# WaterDepthAnalysisBoardv2.net
KiCad netlist of a schematic drawn in Altium Designer
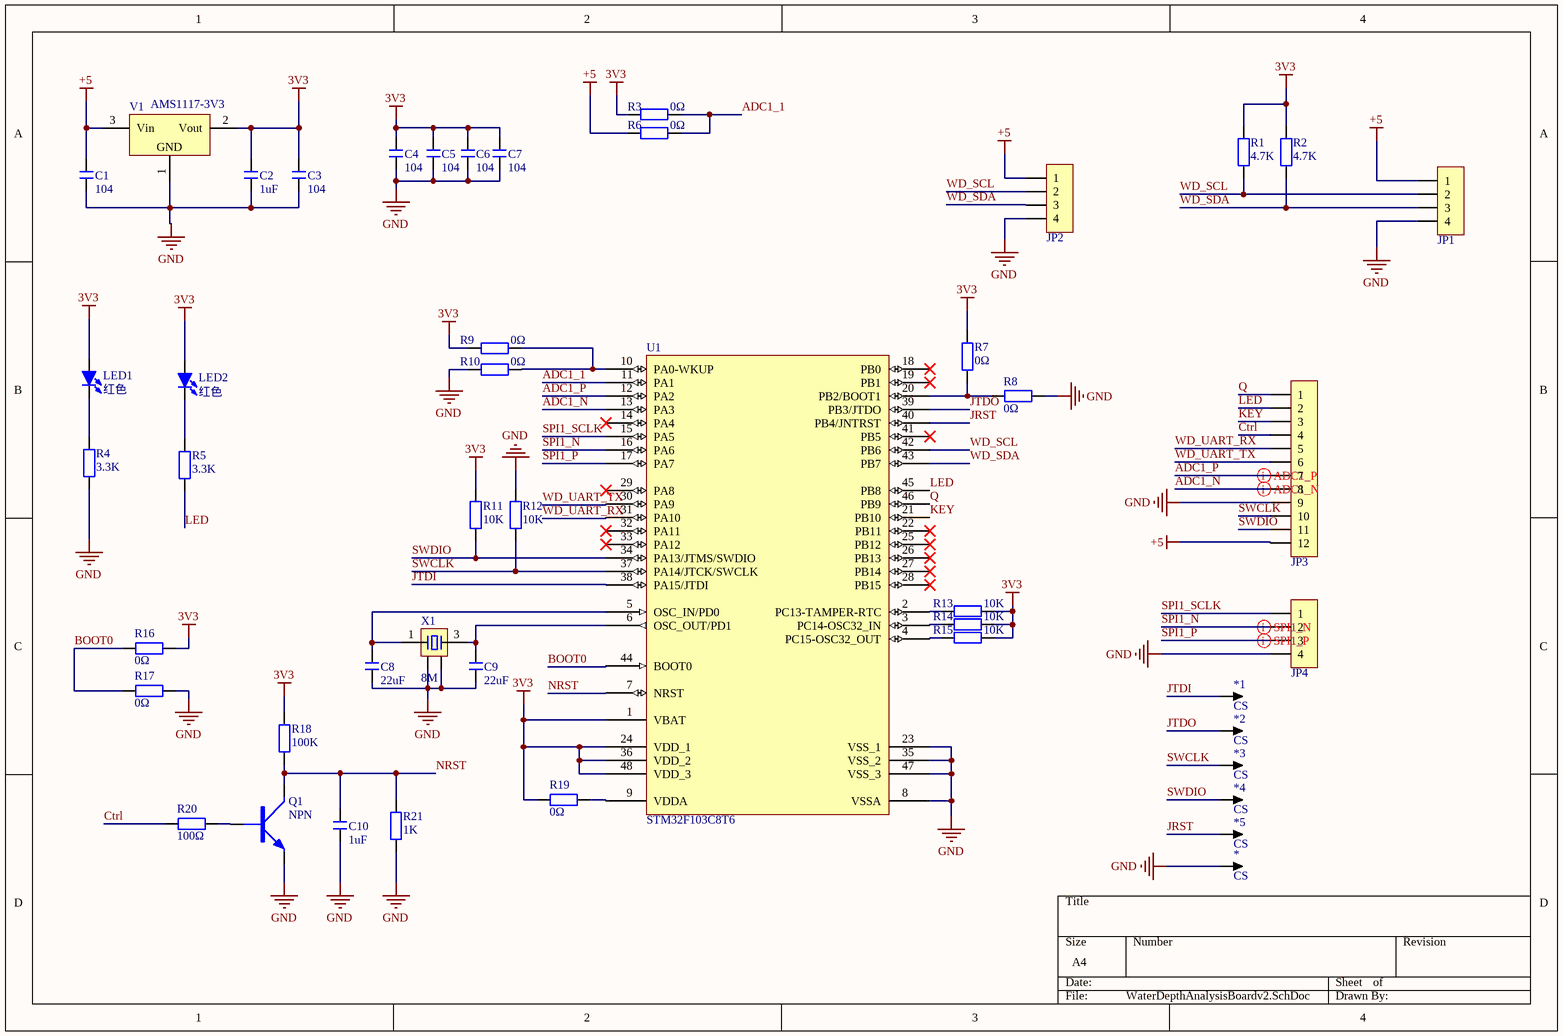
[diagram p0: WaterDepthAnalysisBoardv2.SchDoc]

(export (version "E")
  (design (tool "Eeschema 10.0.6"))
  (components
    (comp (ref "*")
      (value "CS")
      (footprint "R100")
      (description "探针焊盘")
      (fields (field (name "版权归属") "源创客"))
      (libsource (lib "15.1 - 未分类器件") (part "CS"))
    )
    (comp (ref "*1")
      (value "CS")
      (footprint "R100")
      (description "探针焊盘")
      (fields (field (name "版权归属") "源创客"))
      (libsource (lib "15.1 - 未分类器件") (part "CS"))
    )
    (comp (ref "*2")
      (value "CS")
      (footprint "R100")
      (description "探针焊盘")
      (fields (field (name "版权归属") "源创客"))
      (libsource (lib "15.1 - 未分类器件") (part "CS"))
    )
    (comp (ref "*3")
      (value "CS")
      (footprint "R100")
      (description "探针焊盘")
      (fields (field (name "版权归属") "源创客"))
      (libsource (lib "15.1 - 未分类器件") (part "CS"))
    )
    (comp (ref "*4")
      (value "CS")
      (footprint "R100")
      (description "探针焊盘")
      (fields (field (name "版权归属") "源创客"))
      (libsource (lib "15.1 - 未分类器件") (part "CS"))
    )
    (comp (ref "*5")
      (value "CS")
      (footprint "R100")
      (description "探针焊盘")
      (fields (field (name "版权归属") "源创客"))
      (libsource (lib "15.1 - 未分类器件") (part "CS"))
    )
    (comp (ref "C1")
      (value "104")
      (footprint "C 0603_L")
      (description "无极性贴片电容")
      (fields (field (name "版权归属") "源创客"))
      (libsource (lib "3.1   - 电阻-电容-电感") (part "C"))
    )
    (comp (ref "C2")
      (value "1uF")
      (footprint "C 0603_L")
      (description "无极性贴片电容")
      (fields (field (name "版权归属") "源创客"))
      (libsource (lib "3.1   - 电阻-电容-电感") (part "C"))
    )
    (comp (ref "C3")
      (value "104")
      (footprint "C 0603_L")
      (description "无极性贴片电容")
      (fields (field (name "版权归属") "源创客"))
      (libsource (lib "3.1   - 电阻-电容-电感") (part "C"))
    )
    (comp (ref "C4")
      (value "104")
      (footprint "C 0603_L")
      (description "无极性贴片电容")
      (fields (field (name "版权归属") "源创客"))
      (libsource (lib "3.1   - 电阻-电容-电感") (part "C"))
    )
    (comp (ref "C5")
      (value "104")
      (footprint "C 0603_L")
      (description "无极性贴片电容")
      (fields (field (name "版权归属") "源创客"))
      (libsource (lib "3.1   - 电阻-电容-电感") (part "C"))
    )
    (comp (ref "C6")
      (value "104")
      (footprint "C 0603_L")
      (description "无极性贴片电容")
      (fields (field (name "版权归属") "源创客"))
      (libsource (lib "3.1   - 电阻-电容-电感") (part "C"))
    )
    (comp (ref "C7")
      (value "104")
      (footprint "C 0603_L")
      (description "无极性贴片电容")
      (fields (field (name "版权归属") "源创客"))
      (libsource (lib "3.1   - 电阻-电容-电感") (part "C"))
    )
    (comp (ref "C8")
      (value "22uF")
      (footprint "C 0603_L")
      (description "无极性贴片电容")
      (fields (field (name "版权归属") "源创客"))
      (libsource (lib "3.1   - 电阻-电容-电感") (part "C"))
    )
    (comp (ref "C9")
      (value "22uF")
      (footprint "C 0603_L")
      (description "无极性贴片电容")
      (fields (field (name "版权归属") "源创客"))
      (libsource (lib "3.1   - 电阻-电容-电感") (part "C"))
    )
    (comp (ref "C10")
      (value "1uF")
      (footprint "C 0603_L")
      (description "无极性贴片电容")
      (fields (field (name "版权归属") "源创客"))
      (libsource (lib "3.1   - 电阻-电容-电感") (part "C"))
    )
    (comp (ref "JP1")
      (value "HDR-1X4")
      (footprint "MX 1.25-LI-4P")
      (description "4P接插件")
      (fields (field (name "版权归属") "源创客"))
      (libsource (lib "4.2   - 接插件-脚距1.25") (part "Header 4"))
    )
    (comp (ref "JP2")
      (value "HDR-1X4")
      (footprint "MX 1.25-LS-4P")
      (description "4P接插件")
      (fields (field (name "版权归属") "源创客"))
      (libsource (lib "4.2   - 接插件-脚距1.25") (part "Header 4"))
    )
    (comp (ref "JP3")
      (value "HDR-1X12")
      (footprint "HDR2.54-LI-12P")
      (description "12P接插件")
      (fields (field (name "版权归属") "源创客"))
      (libsource (lib "4.5   - 接插件-脚距2.54") (part "Header 12"))
    )
    (comp (ref "JP4")
      (value "HDR-1X4")
      (footprint "HDR2.54-LI-4P")
      (description "4P接插件")
      (fields (field (name "版权归属") "源创客"))
      (libsource (lib "4.5   - 接插件-脚距2.54") (part "Header 4"))
    )
    (comp (ref "LED1")
      (value "红色")
      (footprint "LED 0603W")
      (description "贴片LED")
      (fields (field (name "版权归属") "源创客"))
      (libsource (lib "9.1   - LED") (part "LED-SMD"))
    )
    (comp (ref "LED2")
      (value "红色")
      (footprint "LED 0603W")
      (description "贴片LED")
      (fields (field (name "版权归属") "源创客"))
      (libsource (lib "9.1   - LED") (part "LED-SMD"))
    )
    (comp (ref "Q1")
      (value "NPN")
      (footprint "SOT-23")
      (description "NPN三极管")
      (libsource (lib "三极管") (part "NPN"))
    )
    (comp (ref "R1")
      (value "4.7K")
      (footprint "R 0603_L")
      (description "贴片电阻")
      (fields (field (name "版权归属") "源创客"))
      (libsource (lib "3.1   - 电阻-电容-电感") (part "R"))
    )
    (comp (ref "R2")
      (value "4.7K")
      (footprint "R 0603_L")
      (description "贴片电阻")
      (fields (field (name "版权归属") "源创客"))
      (libsource (lib "3.1   - 电阻-电容-电感") (part "R"))
    )
    (comp (ref "R3")
      (value "0Ω")
      (footprint "R 0603_L")
      (description "贴片电阻")
      (fields (field (name "版权归属") "源创客"))
      (libsource (lib "3.1   - 电阻-电容-电感") (part "R"))
    )
    (comp (ref "R4")
      (value "3.3K")
      (footprint "R 0603_L")
      (description "贴片电阻")
      (fields (field (name "版权归属") "源创客"))
      (libsource (lib "3.1   - 电阻-电容-电感") (part "R"))
    )
    (comp (ref "R5")
      (value "3.3K")
      (footprint "R 0603_L")
      (description "贴片电阻")
      (fields (field (name "版权归属") "源创客"))
      (libsource (lib "3.1   - 电阻-电容-电感") (part "R"))
    )
    (comp (ref "R6")
      (value "0Ω")
      (footprint "R 0603_L")
      (description "贴片电阻")
      (fields (field (name "版权归属") "源创客"))
      (libsource (lib "3.1   - 电阻-电容-电感") (part "R"))
    )
    (comp (ref "R7")
      (value "0Ω")
      (footprint "R 0603_L")
      (description "贴片电阻")
      (fields (field (name "版权归属") "源创客"))
      (libsource (lib "3.1   - 电阻-电容-电感") (part "R"))
    )
    (comp (ref "R8")
      (value "0Ω")
      (footprint "R 0603_L")
      (description "贴片电阻")
      (fields (field (name "版权归属") "源创客"))
      (libsource (lib "3.1   - 电阻-电容-电感") (part "R"))
    )
    (comp (ref "R9")
      (value "0Ω")
      (footprint "R 0603_L")
      (description "贴片电阻")
      (fields (field (name "版权归属") "源创客"))
      (libsource (lib "3.1   - 电阻-电容-电感") (part "R"))
    )
    (comp (ref "R10")
      (value "0Ω")
      (footprint "R 0603_L")
      (description "贴片电阻")
      (fields (field (name "版权归属") "源创客"))
      (libsource (lib "3.1   - 电阻-电容-电感") (part "R"))
    )
    (comp (ref "R11")
      (value "10K")
      (footprint "R 0603_L")
      (description "贴片电阻")
      (fields (field (name "版权归属") "源创客"))
      (libsource (lib "3.1   - 电阻-电容-电感") (part "R"))
    )
    (comp (ref "R12")
      (value "10K")
      (footprint "R 0603_L")
      (description "贴片电阻")
      (fields (field (name "版权归属") "源创客"))
      (libsource (lib "3.1   - 电阻-电容-电感") (part "R"))
    )
    (comp (ref "R13")
      (value "10K")
      (footprint "R 0603_L")
      (description "贴片电阻")
      (fields (field (name "版权归属") "源创客"))
      (libsource (lib "3.1   - 电阻-电容-电感") (part "R"))
    )
    (comp (ref "R14")
      (value "10K")
      (footprint "R 0603_L")
      (description "贴片电阻")
      (fields (field (name "版权归属") "源创客"))
      (libsource (lib "3.1   - 电阻-电容-电感") (part "R"))
    )
    (comp (ref "R15")
      (value "10K")
      (footprint "R 0603_L")
      (description "贴片电阻")
      (fields (field (name "版权归属") "源创客"))
      (libsource (lib "3.1   - 电阻-电容-电感") (part "R"))
    )
    (comp (ref "R16")
      (value "0Ω")
      (footprint "R 0603_L")
      (description "贴片电阻")
      (fields (field (name "版权归属") "源创客"))
      (libsource (lib "3.1   - 电阻-电容-电感") (part "R"))
    )
    (comp (ref "R17")
      (value "0Ω")
      (footprint "R 0603_L")
      (description "贴片电阻")
      (fields (field (name "版权归属") "源创客"))
      (libsource (lib "3.1   - 电阻-电容-电感") (part "R"))
    )
    (comp (ref "R18")
      (value "100K")
      (footprint "R 0603_L")
      (description "贴片电阻")
      (fields (field (name "版权归属") "源创客"))
      (libsource (lib "3.1   - 电阻-电容-电感") (part "R"))
    )
    (comp (ref "R19")
      (value "0Ω")
      (footprint "R 0603_L")
      (description "贴片电阻")
      (fields (field (name "版权归属") "源创客"))
      (libsource (lib "3.1   - 电阻-电容-电感") (part "R"))
    )
    (comp (ref "R20")
      (value "100Ω")
      (footprint "R 0603_L")
      (description "贴片电阻")
      (fields (field (name "版权归属") "源创客"))
      (libsource (lib "3.1   - 电阻-电容-电感") (part "R"))
    )
    (comp (ref "R21")
      (value "1K")
      (footprint "R 0603_L")
      (description "贴片电阻")
      (fields (field (name "版权归属") "源创客"))
      (libsource (lib "3.1   - 电阻-电容-电感") (part "R"))
    )
    (comp (ref "U1")
      (value "STM32F103C8T6")
      (footprint "LQFP48 7X7")
      (libsource (lib "STM32系列") (part "STM32F103C8T6"))
    )
    (comp (ref "V1")
      (value "AMS1117-3V3")
      (footprint "SOT89_N")
      (description "三端稳压芯片")
      (fields (field (name "版权归属") "源创客"))
      (libsource (lib "1.3   - 电源类芯片") (part "AMS1117"))
    )
    (comp (ref "X1")
      (value "8M")
      (footprint "OSC 5032-4P")
      (description "4脚无源晶振")
      (fields (field (name "版权归属") "源创客"))
      (libsource (lib "10.1 - 保险丝-晶振") (part "XTAL-4P"))
    )
  )
  (nets
    (net (code "1") (name "+5") (class "Default")
      (node (ref "C1") (pin "2") (pinfunction "2_2") (pintype "passive"))
      (node (ref "JP1") (pin "1") (pinfunction "1_1") (pintype "passive"))
      (node (ref "JP2") (pin "1") (pinfunction "1_1") (pintype "passive"))
      (node (ref "JP3") (pin "12") (pinfunction "12_12") (pintype "passive"))
      (node (ref "R6") (pin "2") (pinfunction "2_2") (pintype "passive"))
      (node (ref "V1") (pin "3") (pinfunction "Vin_3") (pintype "passive"))
    )
    (net (code "2") (name "/ADC1_1") (class "Default")
      (node (ref "R3") (pin "1") (pinfunction "1_1") (pintype "passive"))
      (node (ref "R6") (pin "1") (pinfunction "1_1") (pintype "passive"))
      (node (ref "U1") (pin "11") (pinfunction "PA1_11") (pintype "bidirectional"))
    )
    (net (code "3") (name "/ADC1_N") (class "Default")
      (node (ref "JP3") (pin "8") (pinfunction "8_8") (pintype "passive"))
      (node (ref "U1") (pin "13") (pinfunction "PA3_13") (pintype "bidirectional"))
    )
    (net (code "4") (name "/ADC1_P") (class "Default")
      (node (ref "JP3") (pin "7") (pinfunction "7_7") (pintype "passive"))
      (node (ref "U1") (pin "12") (pinfunction "PA2_12") (pintype "bidirectional"))
    )
    (net (code "5") (name "/BOOT0") (class "Default")
      (node (ref "R16") (pin "2") (pinfunction "2_2") (pintype "passive"))
      (node (ref "R17") (pin "2") (pinfunction "2_2") (pintype "passive"))
      (node (ref "U1") (pin "44") (pinfunction "BOOT0_44") (pintype "input"))
    )
    (net (code "6") (name "/Ctrl") (class "Default")
      (node (ref "JP3") (pin "4") (pinfunction "4_4") (pintype "passive"))
      (node (ref "R20") (pin "2") (pinfunction "2_2") (pintype "passive"))
    )
    (net (code "7") (name "/JRST") (class "Default")
      (node (ref "*5") (pin "1") (pinfunction "1_1") (pintype "passive"))
      (node (ref "U1") (pin "40") (pinfunction "PB4/JNTRST_40") (pintype "bidirectional"))
    )
    (net (code "8") (name "/JTDI") (class "Default")
      (node (ref "*1") (pin "1") (pinfunction "1_1") (pintype "passive"))
      (node (ref "U1") (pin "38") (pinfunction "PA15/JTDI_38") (pintype "bidirectional"))
    )
    (net (code "9") (name "/JTDO") (class "Default")
      (node (ref "*2") (pin "1") (pinfunction "1_1") (pintype "passive"))
      (node (ref "U1") (pin "39") (pinfunction "PB3/JTDO_39") (pintype "bidirectional"))
    )
    (net (code "10") (name "/KEY") (class "Default")
      (node (ref "JP3") (pin "3") (pinfunction "3_3") (pintype "passive"))
      (node (ref "U1") (pin "21") (pinfunction "PB10_21") (pintype "bidirectional"))
    )
    (net (code "11") (name "/LED") (class "Default")
      (node (ref "JP3") (pin "2") (pinfunction "2_2") (pintype "passive"))
      (node (ref "R5") (pin "1") (pinfunction "1_1") (pintype "passive"))
      (node (ref "U1") (pin "45") (pinfunction "PB8_45") (pintype "bidirectional"))
    )
    (net (code "12") (name "/NRST") (class "Default")
      (node (ref "C10") (pin "2") (pinfunction "2_2") (pintype "passive"))
      (node (ref "Q1") (pin "C") (pinfunction "C_C") (pintype "passive"))
      (node (ref "R18") (pin "2") (pinfunction "2_2") (pintype "passive"))
      (node (ref "R21") (pin "1") (pinfunction "1_1") (pintype "passive"))
      (node (ref "U1") (pin "7") (pinfunction "NRST_7") (pintype "bidirectional"))
    )
    (net (code "13") (name "/Q") (class "Default")
      (node (ref "JP3") (pin "1") (pinfunction "1_1") (pintype "passive"))
      (node (ref "U1") (pin "46") (pinfunction "PB9_46") (pintype "bidirectional"))
    )
    (net (code "14") (name "/SPI1_N") (class "Default")
      (node (ref "JP4") (pin "2") (pinfunction "2_2") (pintype "passive"))
      (node (ref "U1") (pin "16") (pinfunction "PA6_16") (pintype "bidirectional"))
    )
    (net (code "15") (name "/SPI1_P") (class "Default")
      (node (ref "JP4") (pin "3") (pinfunction "3_3") (pintype "passive"))
      (node (ref "U1") (pin "17") (pinfunction "PA7_17") (pintype "bidirectional"))
    )
    (net (code "16") (name "/SPI1_SCLK") (class "Default")
      (node (ref "JP4") (pin "1") (pinfunction "1_1") (pintype "passive"))
      (node (ref "U1") (pin "15") (pinfunction "PA5_15") (pintype "bidirectional"))
    )
    (net (code "17") (name "/SWCLK") (class "Default")
      (node (ref "*3") (pin "1") (pinfunction "1_1") (pintype "passive"))
      (node (ref "JP3") (pin "10") (pinfunction "10_10") (pintype "passive"))
      (node (ref "R12") (pin "2") (pinfunction "2_2") (pintype "passive"))
      (node (ref "U1") (pin "37") (pinfunction "PA14/JTCK/SWCLK_37") (pintype "bidirectional"))
    )
    (net (code "18") (name "/SWDIO") (class "Default")
      (node (ref "*4") (pin "1") (pinfunction "1_1") (pintype "passive"))
      (node (ref "JP3") (pin "11") (pinfunction "11_11") (pintype "passive"))
      (node (ref "R11") (pin "2") (pinfunction "2_2") (pintype "passive"))
      (node (ref "U1") (pin "34") (pinfunction "PA13/JTMS/SWDIO_34") (pintype "bidirectional"))
    )
    (net (code "19") (name "/WD_SCL") (class "Default")
      (node (ref "JP1") (pin "2") (pinfunction "2_2") (pintype "passive"))
      (node (ref "JP2") (pin "2") (pinfunction "2_2") (pintype "passive"))
      (node (ref "R1") (pin "1") (pinfunction "1_1") (pintype "passive"))
      (node (ref "U1") (pin "42") (pinfunction "PB6_42") (pintype "bidirectional"))
    )
    (net (code "20") (name "/WD_SDA") (class "Default")
      (node (ref "JP1") (pin "3") (pinfunction "3_3") (pintype "passive"))
      (node (ref "JP2") (pin "3") (pinfunction "3_3") (pintype "passive"))
      (node (ref "R2") (pin "1") (pinfunction "1_1") (pintype "passive"))
      (node (ref "U1") (pin "43") (pinfunction "PB7_43") (pintype "bidirectional"))
    )
    (net (code "21") (name "/WD_UART_RX") (class "Default")
      (node (ref "JP3") (pin "5") (pinfunction "5_5") (pintype "passive"))
      (node (ref "U1") (pin "31") (pinfunction "PA10_31") (pintype "bidirectional"))
    )
    (net (code "22") (name "/WD_UART_TX") (class "Default")
      (node (ref "JP3") (pin "6") (pinfunction "6_6") (pintype "passive"))
      (node (ref "U1") (pin "30") (pinfunction "PA9_30") (pintype "bidirectional"))
    )
    (net (code "23") (name "3V3") (class "Default")
      (node (ref "C2") (pin "2") (pinfunction "2_2") (pintype "passive"))
      (node (ref "C3") (pin "2") (pinfunction "2_2") (pintype "passive"))
      (node (ref "C4") (pin "2") (pinfunction "2_2") (pintype "passive"))
      (node (ref "C5") (pin "2") (pinfunction "2_2") (pintype "passive"))
      (node (ref "C6") (pin "2") (pinfunction "2_2") (pintype "passive"))
      (node (ref "C7") (pin "2") (pinfunction "2_2") (pintype "passive"))
      (node (ref "LED1") (pin "1") (pinfunction "A_1") (pintype "passive"))
      (node (ref "LED2") (pin "1") (pinfunction "A_1") (pintype "passive"))
      (node (ref "R1") (pin "2") (pinfunction "2_2") (pintype "passive"))
      (node (ref "R11") (pin "1") (pinfunction "1_1") (pintype "passive"))
      (node (ref "R13") (pin "1") (pinfunction "1_1") (pintype "passive"))
      (node (ref "R14") (pin "1") (pinfunction "1_1") (pintype "passive"))
      (node (ref "R15") (pin "1") (pinfunction "1_1") (pintype "passive"))
      (node (ref "R16") (pin "1") (pinfunction "1_1") (pintype "passive"))
      (node (ref "R18") (pin "1") (pinfunction "1_1") (pintype "passive"))
      (node (ref "R19") (pin "2") (pinfunction "2_2") (pintype "passive"))
      (node (ref "R2") (pin "2") (pinfunction "2_2") (pintype "passive"))
      (node (ref "R3") (pin "2") (pinfunction "2_2") (pintype "passive"))
      (node (ref "R7") (pin "1") (pinfunction "1_1") (pintype "passive"))
      (node (ref "R9") (pin "2") (pinfunction "2_2") (pintype "passive"))
      (node (ref "U1") (pin "1") (pinfunction "VBAT_1") (pintype "power_in"))
      (node (ref "U1") (pin "24") (pinfunction "VDD_1_24") (pintype "power_in"))
      (node (ref "U1") (pin "36") (pinfunction "VDD_2_36") (pintype "power_in"))
      (node (ref "U1") (pin "48") (pinfunction "VDD_3_48") (pintype "power_in"))
      (node (ref "V1") (pin "2") (pinfunction "Vout_2") (pintype "passive"))
    )
    (net (code "24") (name "GND") (class "Default")
      (node (ref "*") (pin "1") (pinfunction "1_1") (pintype "passive"))
      (node (ref "C1") (pin "1") (pinfunction "1_1") (pintype "passive"))
      (node (ref "C10") (pin "1") (pinfunction "1_1") (pintype "passive"))
      (node (ref "C2") (pin "1") (pinfunction "1_1") (pintype "passive"))
      (node (ref "C3") (pin "1") (pinfunction "1_1") (pintype "passive"))
      (node (ref "C4") (pin "1") (pinfunction "1_1") (pintype "passive"))
      (node (ref "C5") (pin "1") (pinfunction "1_1") (pintype "passive"))
      (node (ref "C6") (pin "1") (pinfunction "1_1") (pintype "passive"))
      (node (ref "C7") (pin "1") (pinfunction "1_1") (pintype "passive"))
      (node (ref "C8") (pin "1") (pinfunction "1_1") (pintype "passive"))
      (node (ref "C9") (pin "1") (pinfunction "1_1") (pintype "passive"))
      (node (ref "JP1") (pin "4") (pinfunction "4_4") (pintype "passive"))
      (node (ref "JP2") (pin "4") (pinfunction "4_4") (pintype "passive"))
      (node (ref "JP3") (pin "9") (pinfunction "9_9") (pintype "passive"))
      (node (ref "JP4") (pin "4") (pinfunction "4_4") (pintype "passive"))
      (node (ref "Q1") (pin "E") (pinfunction "E_E") (pintype "passive"))
      (node (ref "R10") (pin "2") (pinfunction "2_2") (pintype "passive"))
      (node (ref "R12") (pin "1") (pinfunction "1_1") (pintype "passive"))
      (node (ref "R17") (pin "1") (pinfunction "1_1") (pintype "passive"))
      (node (ref "R21") (pin "2") (pinfunction "2_2") (pintype "passive"))
      (node (ref "R4") (pin "1") (pinfunction "1_1") (pintype "passive"))
      (node (ref "R8") (pin "1") (pinfunction "1_1") (pintype "passive"))
      (node (ref "U1") (pin "23") (pinfunction "VSS_1_23") (pintype "power_in"))
      (node (ref "U1") (pin "35") (pinfunction "VSS_2_35") (pintype "power_in"))
      (node (ref "U1") (pin "47") (pinfunction "VSS_3_47") (pintype "power_in"))
      (node (ref "U1") (pin "8") (pinfunction "VSSA_8") (pintype "power_in"))
      (node (ref "V1") (pin "1") (pinfunction "GND_1") (pintype "passive"))
      (node (ref "X1") (pin "2") (pinfunction "2_2") (pintype "passive"))
      (node (ref "X1") (pin "4") (pinfunction "4_4") (pintype "passive"))
    )
    (net (code "25") (name "Net-(LED1-K)") (class "Default")
      (node (ref "LED1") (pin "2") (pinfunction "K_2") (pintype "passive"))
      (node (ref "R4") (pin "2") (pinfunction "2_2") (pintype "passive"))
    )
    (net (code "26") (name "Net-(LED2-K)") (class "Default")
      (node (ref "LED2") (pin "2") (pinfunction "K_2") (pintype "passive"))
      (node (ref "R5") (pin "2") (pinfunction "2_2") (pintype "passive"))
    )
    (net (code "27") (name "Net-(Q1-PadB)") (class "Default")
      (node (ref "Q1") (pin "B") (pinfunction "B_B") (pintype "passive"))
      (node (ref "R20") (pin "1") (pinfunction "1_1") (pintype "passive"))
    )
    (net (code "28") (name "Net-(U1-OSC_IN{slash}PD0)") (class "Default")
      (node (ref "C8") (pin "2") (pinfunction "2_2") (pintype "passive"))
      (node (ref "U1") (pin "5") (pinfunction "OSC_IN/PD0_5") (pintype "input"))
      (node (ref "X1") (pin "1") (pinfunction "1_1") (pintype "passive"))
    )
    (net (code "29") (name "Net-(U1-OSC_OUT{slash}PD1)") (class "Default")
      (node (ref "C9") (pin "2") (pinfunction "2_2") (pintype "passive"))
      (node (ref "U1") (pin "6") (pinfunction "OSC_OUT/PD1_6") (pintype "output"))
      (node (ref "X1") (pin "3") (pinfunction "3_3") (pintype "passive"))
    )
    (net (code "30") (name "Net-(U1-PA0-WKUP)") (class "Default")
      (node (ref "R10") (pin "1") (pinfunction "1_1") (pintype "passive"))
      (node (ref "R9") (pin "1") (pinfunction "1_1") (pintype "passive"))
      (node (ref "U1") (pin "10") (pinfunction "PA0-WKUP_10") (pintype "bidirectional"))
    )
    (net (code "31") (name "Net-(U1-PB2{slash}BOOT1)") (class "Default")
      (node (ref "R7") (pin "2") (pinfunction "2_2") (pintype "passive"))
      (node (ref "R8") (pin "2") (pinfunction "2_2") (pintype "passive"))
      (node (ref "U1") (pin "20") (pinfunction "PB2/BOOT1_20") (pintype "bidirectional"))
    )
    (net (code "32") (name "Net-(U1-PC13-TAMPER-RTC)") (class "Default")
      (node (ref "R13") (pin "2") (pinfunction "2_2") (pintype "passive"))
      (node (ref "U1") (pin "2") (pinfunction "PC13-TAMPER-RTC_2") (pintype "bidirectional"))
    )
    (net (code "33") (name "Net-(U1-PC14-OSC32_IN)") (class "Default")
      (node (ref "R14") (pin "2") (pinfunction "2_2") (pintype "passive"))
      (node (ref "U1") (pin "3") (pinfunction "PC14-OSC32_IN_3") (pintype "bidirectional"))
    )
    (net (code "34") (name "Net-(U1-PC15-OSC32_OUT)") (class "Default")
      (node (ref "R15") (pin "2") (pinfunction "2_2") (pintype "passive"))
      (node (ref "U1") (pin "4") (pinfunction "PC15-OSC32_OUT_4") (pintype "bidirectional"))
    )
    (net (code "35") (name "Net-(U1-VDDA)") (class "Default")
      (node (ref "R19") (pin "1") (pinfunction "1_1") (pintype "passive"))
      (node (ref "U1") (pin "9") (pinfunction "VDDA_9") (pintype "power_in"))
    )
    (net (code "36") (name "unconnected-(U1-PA4-Pad14)") (class "Default")
      (node (ref "U1") (pin "14") (pinfunction "PA4_14") (pintype "bidirectional+no_connect"))
    )
    (net (code "37") (name "unconnected-(U1-PA8-Pad29)") (class "Default")
      (node (ref "U1") (pin "29") (pinfunction "PA8_29") (pintype "bidirectional+no_connect"))
    )
    (net (code "38") (name "unconnected-(U1-PA11-Pad32)") (class "Default")
      (node (ref "U1") (pin "32") (pinfunction "PA11_32") (pintype "bidirectional+no_connect"))
    )
    (net (code "39") (name "unconnected-(U1-PA12-Pad33)") (class "Default")
      (node (ref "U1") (pin "33") (pinfunction "PA12_33") (pintype "bidirectional+no_connect"))
    )
    (net (code "40") (name "unconnected-(U1-PB0-Pad18)") (class "Default")
      (node (ref "U1") (pin "18") (pinfunction "PB0_18") (pintype "bidirectional+no_connect"))
    )
    (net (code "41") (name "unconnected-(U1-PB1-Pad19)") (class "Default")
      (node (ref "U1") (pin "19") (pinfunction "PB1_19") (pintype "bidirectional+no_connect"))
    )
    (net (code "42") (name "unconnected-(U1-PB5-Pad41)") (class "Default")
      (node (ref "U1") (pin "41") (pinfunction "PB5_41") (pintype "bidirectional+no_connect"))
    )
    (net (code "43") (name "unconnected-(U1-PB11-Pad22)") (class "Default")
      (node (ref "U1") (pin "22") (pinfunction "PB11_22") (pintype "bidirectional+no_connect"))
    )
    (net (code "44") (name "unconnected-(U1-PB12-Pad25)") (class "Default")
      (node (ref "U1") (pin "25") (pinfunction "PB12_25") (pintype "bidirectional+no_connect"))
    )
    (net (code "45") (name "unconnected-(U1-PB13-Pad26)") (class "Default")
      (node (ref "U1") (pin "26") (pinfunction "PB13_26") (pintype "bidirectional+no_connect"))
    )
    (net (code "46") (name "unconnected-(U1-PB14-Pad27)") (class "Default")
      (node (ref "U1") (pin "27") (pinfunction "PB14_27") (pintype "bidirectional+no_connect"))
    )
    (net (code "47") (name "unconnected-(U1-PB15-Pad28)") (class "Default")
      (node (ref "U1") (pin "28") (pinfunction "PB15_28") (pintype "bidirectional+no_connect"))
    )
  )
)
